# ultrasonic_imu_sensor.net
KiCad netlist of a schematic drawn in Altium Designer
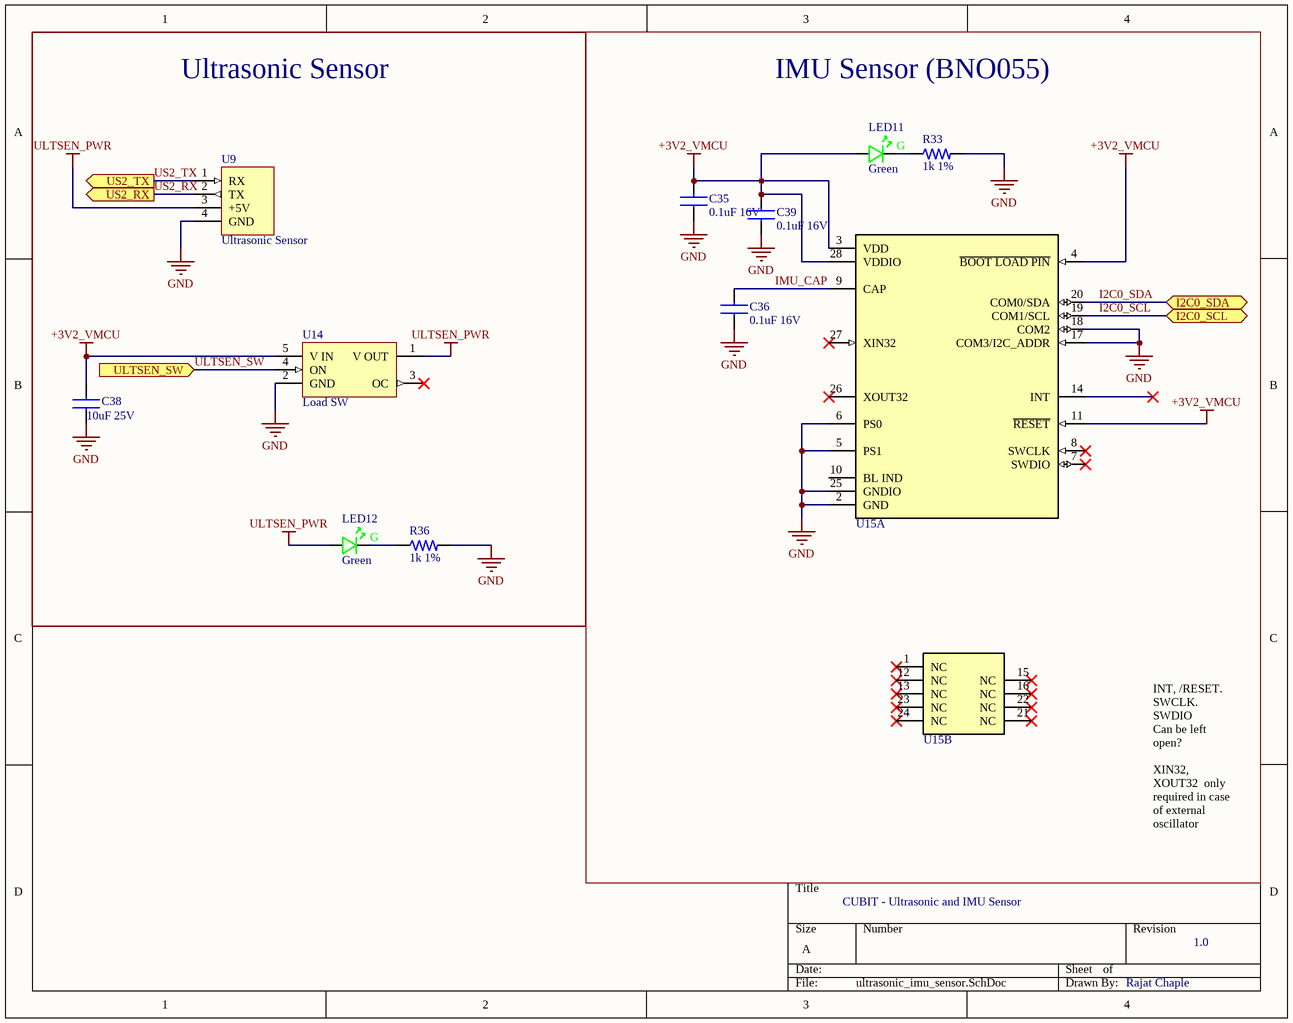
[diagram p0: ultrasonic_imu_sensor.SchDoc]

(export (version "E")
  (design (tool "Eeschema 10.0.6"))
  (components
    (comp (ref "C35")
      (value "0.1uF 16V")
      (footprint "LPEDT_proj_lib:CAP_0603_1MM")
      (description "Cap Ceramic 0.1uF 16V X7R 10% SMD 0603 125°C Paper T/R")
      (fields
        (field (name "MANUFACTURER") "KEMET")
        (field (name "MANUFACTURER PART NUMBER") "C0805C104K4RACAUTO")
      )
      (libsource (lib "LPEDT_proj_lib") (part "C0805C104K4RACAUTO"))
    )
    (comp (ref "C36")
      (value "0.1uF 16V")
      (footprint "LPEDT_proj_lib:CAP_0603_1MM")
      (description "Cap Ceramic 0.1uF 16V X7R 10% SMD 0603 125°C Paper T/R")
      (fields
        (field (name "MANUFACTURER") "KEMET")
        (field (name "MANUFACTURER PART NUMBER") "C0805C104K4RACAUTO")
      )
      (libsource (lib "LPEDT_proj_lib") (part "C0805C104K4RACAUTO"))
    )
    (comp (ref "C38")
      (value "10uF 25V")
      (footprint "LPEDT_proj_lib:CAP_0805_02X125")
      (description "Cap 0805 25 V 10 uF ±20% Tolerance X5R Monolithic Ceramic Chip Capacitor")
      (fields
        (field (name "MANUFACTURER") "Murata")
        (field (name "MANUFACTURER PART NUMBER") "GRM21BR61E106KA73K")
      )
      (libsource (lib "LPEDT_proj_lib") (part "GRM21BR61E106KA73K"))
    )
    (comp (ref "C39")
      (value "0.1uF 16V")
      (footprint "LPEDT_proj_lib:CAP_0603_1MM")
      (description "Cap Ceramic 0.1uF 16V X7R 10% SMD 0603 125°C Paper T/R")
      (fields
        (field (name "MANUFACTURER") "KEMET")
        (field (name "MANUFACTURER PART NUMBER") "C0805C104K4RACAUTO")
      )
      (libsource (lib "LPEDT_proj_lib") (part "C0805C104K4RACAUTO"))
    )
    (comp (ref "LED11")
      (value "Green")
      (footprint "LED_0603_RED_WL-SMCW")
      (description "Led Green Clear 0603 SMD")
      (fields
        (field (name "MANUFACTURER") "QT-Brightek")
        (field (name "MANUFACTURER PART NUMBER") "QBLP601-AG1")
      )
      (libsource (lib "LPEDT_proj_lib") (part "QBLP601-AG1"))
    )
    (comp (ref "LED12")
      (value "Green")
      (footprint "LED_0603_RED_WL-SMCW")
      (description "Led Green Clear 0603 SMD")
      (fields
        (field (name "MANUFACTURER") "QT-Brightek")
        (field (name "MANUFACTURER PART NUMBER") "QBLP601-AG1")
      )
      (libsource (lib "LPEDT_proj_lib") (part "QBLP601-AG1"))
    )
    (comp (ref "R33")
      (value "1k 1%")
      (footprint "2_Chip_0603_RMCF")
      (description "Res 1K Ohm 1% 0.1W(1/10W) ±100ppm/C Pad SMD Automotive T/R")
      (fields
        (field (name "MANUFACTURER") "Stackpole Electronics")
        (field (name "MANUFACTURER PART NUMBER") "RMCF0603FT1K00")
      )
      (libsource (lib "LPEDT_proj_lib") (part "RMCF0603FT1K00"))
    )
    (comp (ref "R36")
      (value "1k 1%")
      (footprint "2_Chip_0603_RMCF")
      (description "Res 1K Ohm 1% 0.1W(1/10W) ±100ppm/C Pad SMD Automotive T/R")
      (fields
        (field (name "MANUFACTURER") "Stackpole Electronics")
        (field (name "MANUFACTURER PART NUMBER") "RMCF0603FT1K00")
      )
      (libsource (lib "LPEDT_proj_lib") (part "RMCF0603FT1K00"))
    )
    (comp (ref "U9")
      (value "Ultrasonic Sensor")
      (footprint "4_PIN_100MIL")
      (libsource (lib "LPEDT_proj_lib") (part "Ultrasonic Sensor"))
    )
    (comp (ref "U14")
      (value "Load SW")
      (footprint "SOT65P210X110-5N")
      (description "5.5-V, 0.1-A, 500-mΩ, load switch with current limit and active low enable 5-SC70 -40 to 85")
      (fields
        (field (name "MANUFACTURER") "Texas Instruments")
        (field (name "MANUFACTURER PART NUMBER") "TPS22942DCKR")
      )
      (libsource (lib "LPEDT_proj_lib") (part "TPS22942DCKR"))
    )
    (comp (ref "U15")
      (value "BNO005")
      (footprint "LGA28R50P4X10_380X520X100")
      (libsource (lib "LPEDT_proj_lib") (part "BNO055"))
    )
  )
  (nets
    (net (code "1") (name "+3V2_VMCU") (class "Default")
      (node (ref "C35") (pin "1") (pinfunction "1_1") (pintype "passive"))
      (node (ref "C38") (pin "1") (pinfunction "1_1") (pintype "passive"))
      (node (ref "C39") (pin "1") (pinfunction "1_1") (pintype "passive"))
      (node (ref "LED11") (pin "A") (pinfunction "A_A") (pintype "passive"))
      (node (ref "U14") (pin "5") (pinfunction "V_IN_5") (pintype "power_in"))
      (node (ref "U15") (pin "11") (pinfunction "~{RESET}_11") (pintype "input"))
      (node (ref "U15") (pin "28") (pinfunction "VDDIO_28") (pintype "power_in"))
      (node (ref "U15") (pin "3") (pinfunction "VDD_3") (pintype "power_in"))
      (node (ref "U15") (pin "4") (pinfunction "~{BOOT_LOAD_PIN}_4") (pintype "input"))
    )
    (net (code "2") (name "/I2C0_SCL") (class "Default")
      (node (ref "U15") (pin "19") (pinfunction "COM1/SCL_19") (pintype "bidirectional"))
    )
    (net (code "3") (name "/I2C0_SDA") (class "Default")
      (node (ref "U15") (pin "20") (pinfunction "COM0/SDA_20") (pintype "bidirectional"))
    )
    (net (code "4") (name "/IMU_CAP") (class "Default")
      (node (ref "C36") (pin "1") (pinfunction "1_1") (pintype "passive"))
      (node (ref "U15") (pin "9") (pinfunction "CAP_9") (pintype "passive"))
    )
    (net (code "5") (name "/ULTSEN_SW") (class "Default")
      (node (ref "U14") (pin "4") (pinfunction "ON_4") (pintype "input"))
    )
    (net (code "6") (name "/US2_RX") (class "Default")
      (node (ref "U9") (pin "2") (pinfunction "TX_2") (pintype "output"))
    )
    (net (code "7") (name "/US2_TX") (class "Default")
      (node (ref "U9") (pin "1") (pinfunction "RX_1") (pintype "input"))
    )
    (net (code "8") (name "GND") (class "Default")
      (node (ref "C35") (pin "2") (pinfunction "2_2") (pintype "passive"))
      (node (ref "C36") (pin "2") (pinfunction "2_2") (pintype "passive"))
      (node (ref "C38") (pin "2") (pinfunction "2_2") (pintype "passive"))
      (node (ref "C39") (pin "2") (pinfunction "2_2") (pintype "passive"))
      (node (ref "R33") (pin "2") (pinfunction "2_2") (pintype "passive"))
      (node (ref "R36") (pin "2") (pinfunction "2_2") (pintype "passive"))
      (node (ref "U14") (pin "2") (pinfunction "GND_2") (pintype "power_in"))
      (node (ref "U15") (pin "17") (pinfunction "COM3/I2C_ADDR_17") (pintype "input"))
      (node (ref "U15") (pin "18") (pinfunction "COM2_18") (pintype "bidirectional"))
      (node (ref "U15") (pin "2") (pinfunction "GND_2") (pintype "power_in"))
      (node (ref "U15") (pin "25") (pinfunction "GNDIO_25") (pintype "power_in"))
      (node (ref "U15") (pin "5") (pinfunction "PS1_5") (pintype "power_in"))
      (node (ref "U15") (pin "6") (pinfunction "PS0_6") (pintype "power_in"))
      (node (ref "U9") (pin "4") (pinfunction "GND_4") (pintype "power_in"))
    )
    (net (code "9") (name "Net-(LED11-PadC)") (class "Default")
      (node (ref "LED11") (pin "C") (pinfunction "C_C") (pintype "passive"))
      (node (ref "R33") (pin "1") (pinfunction "1_1") (pintype "passive"))
    )
    (net (code "10") (name "Net-(LED12-PadC)") (class "Default")
      (node (ref "LED12") (pin "C") (pinfunction "C_C") (pintype "passive"))
      (node (ref "R36") (pin "1") (pinfunction "1_1") (pintype "passive"))
    )
    (net (code "11") (name "ULTSEN_PWR") (class "Default")
      (node (ref "LED12") (pin "A") (pinfunction "A_A") (pintype "passive"))
      (node (ref "U14") (pin "1") (pinfunction "V_OUT_1") (pintype "power_in"))
      (node (ref "U9") (pin "3") (pinfunction "+5V_3") (pintype "power_in"))
    )
    (net (code "12") (name "unconnected-(U14-OC-Pad3)") (class "Default")
      (node (ref "U14") (pin "3") (pinfunction "OC_3") (pintype "output+no_connect"))
    )
    (net (code "13") (name "unconnected-(U15A-BL_IND-Pad10)") (class "Default")
      (node (ref "U15") (pin "10") (pinfunction "BL_IND_10") (pintype "power_in"))
    )
    (net (code "14") (name "unconnected-(U15A-INT-Pad14)") (class "Default")
      (node (ref "U15") (pin "14") (pinfunction "INT_14") (pintype "passive+no_connect"))
    )
    (net (code "15") (name "unconnected-(U15A-SWCLK-Pad8)") (class "Default")
      (node (ref "U15") (pin "8") (pinfunction "SWCLK_8") (pintype "input+no_connect"))
    )
    (net (code "16") (name "unconnected-(U15A-SWDIO-Pad7)") (class "Default")
      (node (ref "U15") (pin "7") (pinfunction "SWDIO_7") (pintype "bidirectional+no_connect"))
    )
    (net (code "17") (name "unconnected-(U15A-XIN32-Pad27)") (class "Default")
      (node (ref "U15") (pin "27") (pinfunction "XIN32_27") (pintype "input+no_connect"))
    )
    (net (code "18") (name "unconnected-(U15A-XOUT32-Pad26)") (class "Default")
      (node (ref "U15") (pin "26") (pinfunction "XOUT32_26") (pintype "passive+no_connect"))
    )
    (net (code "19") (name "unconnected-(U15B-NC-Pad1)") (class "Default")
      (node (ref "U15") (pin "1") (pinfunction "NC_1") (pintype "passive+no_connect"))
    )
    (net (code "20") (name "unconnected-(U15B-NC-Pad12)") (class "Default")
      (node (ref "U15") (pin "12") (pinfunction "NC_12") (pintype "passive+no_connect"))
    )
    (net (code "21") (name "unconnected-(U15B-NC-Pad13)") (class "Default")
      (node (ref "U15") (pin "13") (pinfunction "NC_13") (pintype "passive+no_connect"))
    )
    (net (code "22") (name "unconnected-(U15B-NC-Pad15)") (class "Default")
      (node (ref "U15") (pin "15") (pinfunction "NC_15") (pintype "passive+no_connect"))
    )
    (net (code "23") (name "unconnected-(U15B-NC-Pad16)") (class "Default")
      (node (ref "U15") (pin "16") (pinfunction "NC_16") (pintype "passive+no_connect"))
    )
    (net (code "24") (name "unconnected-(U15B-NC-Pad21)") (class "Default")
      (node (ref "U15") (pin "21") (pinfunction "NC_21") (pintype "passive+no_connect"))
    )
    (net (code "25") (name "unconnected-(U15B-NC-Pad22)") (class "Default")
      (node (ref "U15") (pin "22") (pinfunction "NC_22") (pintype "passive+no_connect"))
    )
    (net (code "26") (name "unconnected-(U15B-NC-Pad23)") (class "Default")
      (node (ref "U15") (pin "23") (pinfunction "NC_23") (pintype "passive+no_connect"))
    )
    (net (code "27") (name "unconnected-(U15B-NC-Pad24)") (class "Default")
      (node (ref "U15") (pin "24") (pinfunction "NC_24") (pintype "passive+no_connect"))
    )
  )
)
